# Sheet2.net
KiCad netlist of a schematic drawn in Altium Designer
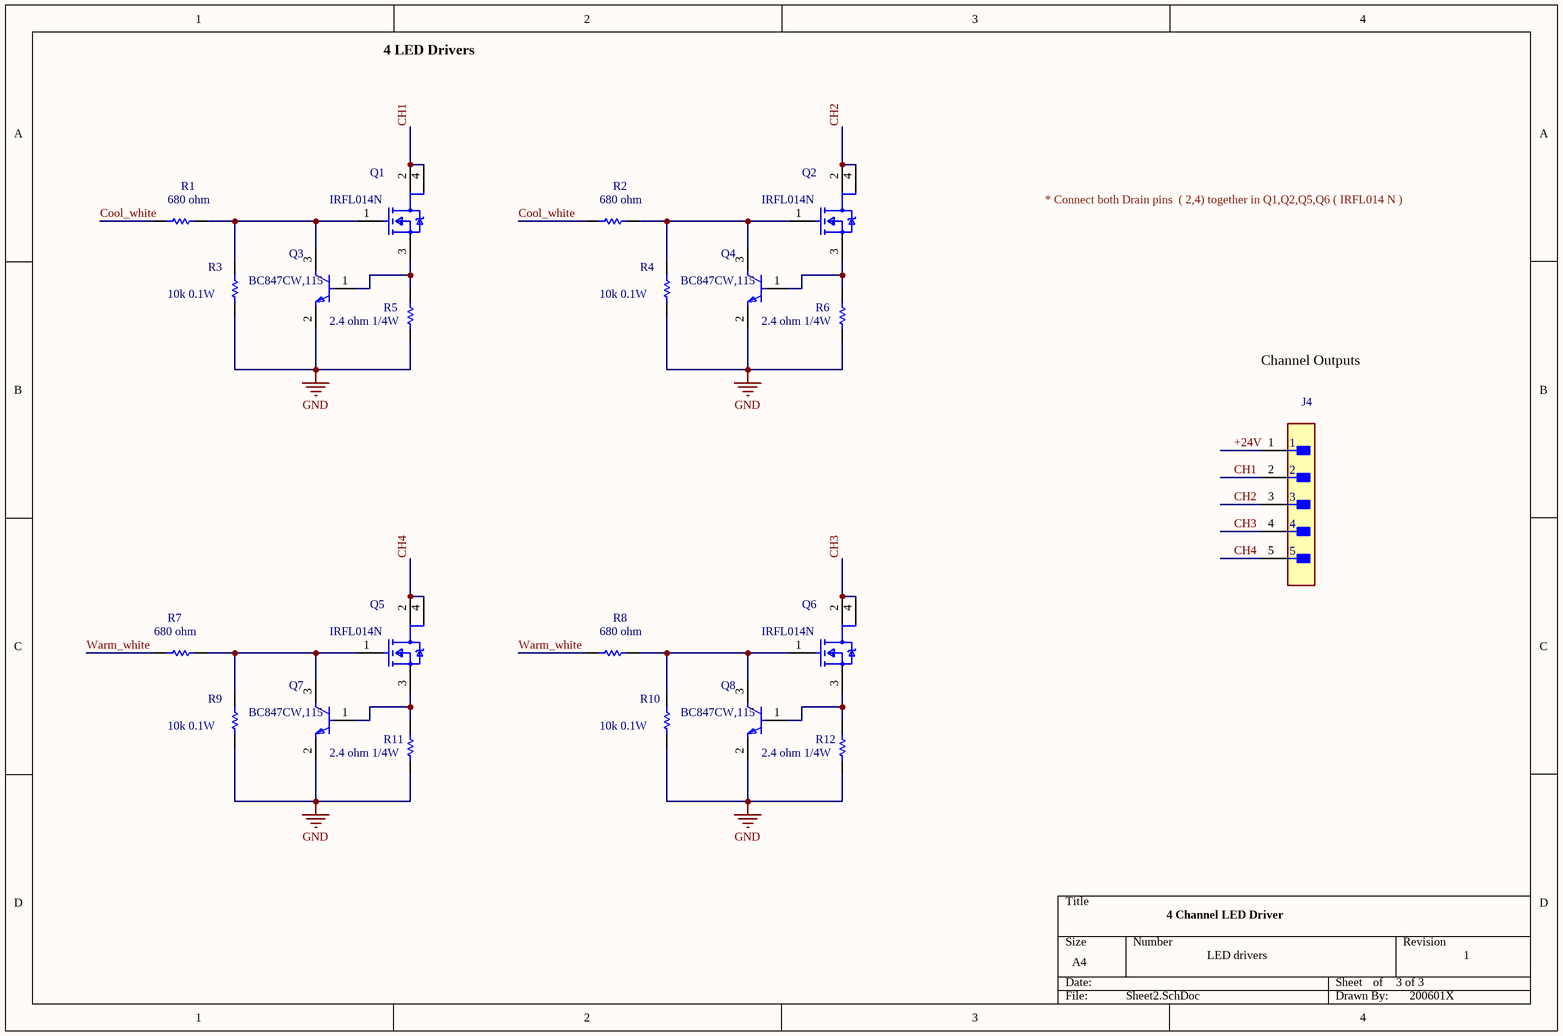
[diagram p0: Sheet2.SchDoc]

(export (version "E")
  (design (tool "Eeschema 10.0.6"))
  (components
    (comp (ref "J4")
      (value "B5B-XH-AM(LF)(SN)")
      (footprint "FP-B5B-XH-AM_LF_SN-MFG")
      (description "CONN HEADER VERT 5POS 2.5MM")
      (libsource (lib "Altium Content Vault") (part "bf93c07fd2649a848d0ec8585582aab"))
    )
    (comp (ref "Q1")
      (value "IRFL014N")
      (footprint "FP-P-SOT223-3-MFG")
      (description "MOSFET N-CH 55V 1.9A SOT223")
      (fields
        (field (name "OCTOPART") "https://octopart.com/irfl014ntrpbf-infineon-65874001")
        (field (name "MANUFACTURER") "Infineon")
      )
      (libsource (lib "Altium Content Vault") (part "fc5d98a743b914d40cd554a2414dc7e"))
    )
    (comp (ref "Q2")
      (value "IRFL014N")
      (footprint "FP-P-SOT223-3-MFG")
      (description "MOSFET N-CH 55V 1.9A SOT223")
      (fields
        (field (name "OCTOPART") "https://octopart.com/irfl014ntrpbf-infineon-65874001")
        (field (name "MANUFACTURER") "Infineon")
      )
      (libsource (lib "Altium Content Vault") (part "fc5d98a743b914d40cd554a2414dc7e"))
    )
    (comp (ref "Q3")
      (value "BC847CW,115")
      (footprint "FP-SOT323-IPC_A")
      (description "TRANS NPN 45V 100MA SOT323")
      (libsource (lib "Altium Content Vault") (part "b44e953556f554d0102664c7d152cb4"))
    )
    (comp (ref "Q4")
      (value "BC847CW,115")
      (footprint "FP-SOT323-IPC_A")
      (description "TRANS NPN 45V 100MA SOT323")
      (libsource (lib "Altium Content Vault") (part "b44e953556f554d0102664c7d152cb4"))
    )
    (comp (ref "Q5")
      (value "IRFL014N")
      (footprint "FP-P-SOT223-3-MFG")
      (description "MOSFET N-CH 55V 1.9A SOT223")
      (fields
        (field (name "OCTOPART") "https://octopart.com/irfl014ntrpbf-infineon-65874001")
        (field (name "MANUFACTURER") "Infineon")
      )
      (libsource (lib "Altium Content Vault") (part "fc5d98a743b914d40cd554a2414dc7e"))
    )
    (comp (ref "Q6")
      (value "IRFL014N")
      (footprint "FP-P-SOT223-3-MFG")
      (description "MOSFET N-CH 55V 1.9A SOT223")
      (fields
        (field (name "OCTOPART") "https://octopart.com/irfl014ntrpbf-infineon-65874001")
        (field (name "MANUFACTURER") "Infineon")
      )
      (libsource (lib "Altium Content Vault") (part "fc5d98a743b914d40cd554a2414dc7e"))
    )
    (comp (ref "Q7")
      (value "BC847CW,115")
      (footprint "FP-SOT323-IPC_A")
      (description "TRANS NPN 45V 100MA SOT323")
      (libsource (lib "Altium Content Vault") (part "b44e953556f554d0102664c7d152cb4"))
    )
    (comp (ref "Q8")
      (value "BC847CW,115")
      (footprint "FP-SOT323-IPC_A")
      (description "TRANS NPN 45V 100MA SOT323")
      (libsource (lib "Altium Content Vault") (part "b44e953556f554d0102664c7d152cb4"))
    )
    (comp (ref "R1")
      (value "680 ohm")
      (footprint "RESC2013X50X30NL20T20")
      (fields (field (name "MANUFACTURER") "Vishay Dale") (field (name "PART NUMBER") "CRCW0805680RFKEA"))
      (libsource (lib "Altium Content Vault") (part "RES"))
    )
    (comp (ref "R2")
      (value "680 ohm")
      (footprint "RESC2013X50X30NL20T20")
      (fields (field (name "MANUFACTURER") "Vishay Dale") (field (name "PART NUMBER") "CRCW0805680RFKEA"))
      (libsource (lib "Altium Content Vault") (part "RES"))
    )
    (comp (ref "R3")
      (value "10k 0.1W")
      (footprint "RESC1609X50X30NL8T20")
      (description "Chip Resistor, 10 KOhm, +/- 1%, 100 mW, -55 to 155 degC, 0603 (1608 Metric), RoHS, Tape and Reel")
      (fields (field (name "MANUFACTURER") "Vishay Semiconductor"))
      (libsource (lib "Altium Content Vault") (part "RES-2"))
    )
    (comp (ref "R4")
      (value "10k 0.1W")
      (footprint "RESC1609X50X30NL8T20")
      (description "Chip Resistor, 10 KOhm, +/- 1%, 100 mW, -55 to 155 degC, 0603 (1608 Metric), RoHS, Tape and Reel")
      (fields (field (name "MANUFACTURER") "Vishay Semiconductor"))
      (libsource (lib "Altium Content Vault") (part "RES-2"))
    )
    (comp (ref "R5")
      (value "2.4 ohm 1/4W")
      (footprint "RESC3116X65X40LL10T20")
      (fields (field (name "MANUFACTURER") "Yageo") (field (name "PART NUMBER") "RC1206FR-072R4L"))
      (libsource (lib "Altium Content Vault") (part "RES"))
    )
    (comp (ref "R6")
      (value "2.4 ohm 1/4W")
      (footprint "RESC3116X65X40LL10T20")
      (fields (field (name "MANUFACTURER") "Yageo") (field (name "PART NUMBER") "RC1206FR-072R4L"))
      (libsource (lib "Altium Content Vault") (part "RES"))
    )
    (comp (ref "R7")
      (value "680 ohm")
      (footprint "RESC2013X50X30NL20T20")
      (fields (field (name "MANUFACTURER") "Vishay Dale") (field (name "PART NUMBER") "CRCW0805680RFKEA"))
      (libsource (lib "Altium Content Vault") (part "RES"))
    )
    (comp (ref "R8")
      (value "680 ohm")
      (footprint "RESC2013X50X30NL20T20")
      (fields (field (name "MANUFACTURER") "Vishay Dale") (field (name "PART NUMBER") "CRCW0805680RFKEA"))
      (libsource (lib "Altium Content Vault") (part "RES"))
    )
    (comp (ref "R9")
      (value "10k 0.1W")
      (footprint "RESC1609X50X30NL8T20")
      (description "Chip Resistor, 10 KOhm, +/- 1%, 100 mW, -55 to 155 degC, 0603 (1608 Metric), RoHS, Tape and Reel")
      (fields (field (name "MANUFACTURER") "Vishay Semiconductor"))
      (libsource (lib "Altium Content Vault") (part "RES-2"))
    )
    (comp (ref "R10")
      (value "10k 0.1W")
      (footprint "RESC1609X50X30NL8T20")
      (description "Chip Resistor, 10 KOhm, +/- 1%, 100 mW, -55 to 155 degC, 0603 (1608 Metric), RoHS, Tape and Reel")
      (fields (field (name "MANUFACTURER") "Vishay Semiconductor"))
      (libsource (lib "Altium Content Vault") (part "RES-2"))
    )
    (comp (ref "R11")
      (value "2.4 ohm 1/4W")
      (footprint "RESC3116X65X40LL10T20")
      (fields (field (name "MANUFACTURER") "Yageo") (field (name "PART NUMBER") "RC1206FR-072R4L"))
      (libsource (lib "Altium Content Vault") (part "RES"))
    )
    (comp (ref "R12")
      (value "2.4 ohm 1/4W")
      (footprint "RESC3116X65X40LL10T20")
      (fields (field (name "MANUFACTURER") "Yageo") (field (name "PART NUMBER") "RC1206FR-072R4L"))
      (libsource (lib "Altium Content Vault") (part "RES"))
    )
  )
  (nets
    (net (code "1") (name "/+24V") (class "Default")
      (node (ref "J4") (pin "1") (pinfunction "1_1") (pintype "passive"))
    )
    (net (code "2") (name "/CH1") (class "Default")
      (node (ref "J4") (pin "2") (pinfunction "2_2") (pintype "passive"))
      (node (ref "Q1") (pin "2") (pinfunction "DRAIN_2") (pintype "passive"))
      (node (ref "Q1") (pin "4") (pinfunction "DRAIN_4") (pintype "passive"))
    )
    (net (code "3") (name "/CH2") (class "Default")
      (node (ref "J4") (pin "3") (pinfunction "3_3") (pintype "passive"))
      (node (ref "Q2") (pin "2") (pinfunction "DRAIN_2") (pintype "passive"))
      (node (ref "Q2") (pin "4") (pinfunction "DRAIN_4") (pintype "passive"))
    )
    (net (code "4") (name "/CH3") (class "Default")
      (node (ref "J4") (pin "4") (pinfunction "4_4") (pintype "passive"))
      (node (ref "Q6") (pin "2") (pinfunction "DRAIN_2") (pintype "passive"))
      (node (ref "Q6") (pin "4") (pinfunction "DRAIN_4") (pintype "passive"))
    )
    (net (code "5") (name "/CH4") (class "Default")
      (node (ref "J4") (pin "5") (pinfunction "5_5") (pintype "passive"))
      (node (ref "Q5") (pin "2") (pinfunction "DRAIN_2") (pintype "passive"))
      (node (ref "Q5") (pin "4") (pinfunction "DRAIN_4") (pintype "passive"))
    )
    (net (code "6") (name "/Cool_white") (class "Default")
      (node (ref "R1") (pin "1") (pinfunction "1_1") (pintype "passive"))
      (node (ref "R2") (pin "1") (pinfunction "1_1") (pintype "passive"))
    )
    (net (code "7") (name "/Warm_white") (class "Default")
      (node (ref "R7") (pin "1") (pinfunction "1_1") (pintype "passive"))
      (node (ref "R8") (pin "1") (pinfunction "1_1") (pintype "passive"))
    )
    (net (code "8") (name "GND") (class "Default")
      (node (ref "Q3") (pin "2") (pinfunction "E_2") (pintype "passive"))
      (node (ref "Q4") (pin "2") (pinfunction "E_2") (pintype "passive"))
      (node (ref "Q7") (pin "2") (pinfunction "E_2") (pintype "passive"))
      (node (ref "Q8") (pin "2") (pinfunction "E_2") (pintype "passive"))
      (node (ref "R10") (pin "1") (pinfunction "1_1") (pintype "passive"))
      (node (ref "R11") (pin "1") (pinfunction "1_1") (pintype "passive"))
      (node (ref "R12") (pin "1") (pinfunction "1_1") (pintype "passive"))
      (node (ref "R3") (pin "1") (pinfunction "1_1") (pintype "passive"))
      (node (ref "R4") (pin "1") (pinfunction "1_1") (pintype "passive"))
      (node (ref "R5") (pin "1") (pinfunction "1_1") (pintype "passive"))
      (node (ref "R6") (pin "1") (pinfunction "1_1") (pintype "passive"))
      (node (ref "R9") (pin "1") (pinfunction "1_1") (pintype "passive"))
    )
    (net (code "9") (name "Net-(Q1-GATE)") (class "Default")
      (node (ref "Q1") (pin "1") (pinfunction "GATE_1") (pintype "passive"))
      (node (ref "Q3") (pin "3") (pinfunction "C_3") (pintype "passive"))
      (node (ref "R1") (pin "2") (pinfunction "2_2") (pintype "passive"))
      (node (ref "R3") (pin "2") (pinfunction "2_2") (pintype "passive"))
    )
    (net (code "10") (name "Net-(Q1-SOURCE)") (class "Default")
      (node (ref "Q1") (pin "3") (pinfunction "SOURCE_3") (pintype "passive"))
      (node (ref "Q3") (pin "1") (pinfunction "B_1") (pintype "passive"))
      (node (ref "R5") (pin "2") (pinfunction "2_2") (pintype "passive"))
    )
    (net (code "11") (name "Net-(Q2-GATE)") (class "Default")
      (node (ref "Q2") (pin "1") (pinfunction "GATE_1") (pintype "passive"))
      (node (ref "Q4") (pin "3") (pinfunction "C_3") (pintype "passive"))
      (node (ref "R2") (pin "2") (pinfunction "2_2") (pintype "passive"))
      (node (ref "R4") (pin "2") (pinfunction "2_2") (pintype "passive"))
    )
    (net (code "12") (name "Net-(Q2-SOURCE)") (class "Default")
      (node (ref "Q2") (pin "3") (pinfunction "SOURCE_3") (pintype "passive"))
      (node (ref "Q4") (pin "1") (pinfunction "B_1") (pintype "passive"))
      (node (ref "R6") (pin "2") (pinfunction "2_2") (pintype "passive"))
    )
    (net (code "13") (name "Net-(Q5-GATE)") (class "Default")
      (node (ref "Q5") (pin "1") (pinfunction "GATE_1") (pintype "passive"))
      (node (ref "Q7") (pin "3") (pinfunction "C_3") (pintype "passive"))
      (node (ref "R7") (pin "2") (pinfunction "2_2") (pintype "passive"))
      (node (ref "R9") (pin "2") (pinfunction "2_2") (pintype "passive"))
    )
    (net (code "14") (name "Net-(Q5-SOURCE)") (class "Default")
      (node (ref "Q5") (pin "3") (pinfunction "SOURCE_3") (pintype "passive"))
      (node (ref "Q7") (pin "1") (pinfunction "B_1") (pintype "passive"))
      (node (ref "R11") (pin "2") (pinfunction "2_2") (pintype "passive"))
    )
    (net (code "15") (name "Net-(Q6-GATE)") (class "Default")
      (node (ref "Q6") (pin "1") (pinfunction "GATE_1") (pintype "passive"))
      (node (ref "Q8") (pin "3") (pinfunction "C_3") (pintype "passive"))
      (node (ref "R10") (pin "2") (pinfunction "2_2") (pintype "passive"))
      (node (ref "R8") (pin "2") (pinfunction "2_2") (pintype "passive"))
    )
    (net (code "16") (name "Net-(Q6-SOURCE)") (class "Default")
      (node (ref "Q6") (pin "3") (pinfunction "SOURCE_3") (pintype "passive"))
      (node (ref "Q8") (pin "1") (pinfunction "B_1") (pintype "passive"))
      (node (ref "R12") (pin "2") (pinfunction "2_2") (pintype "passive"))
    )
  )
)
